# tinypico-fc.net
KiCad netlist of a schematic drawn in EAGLE
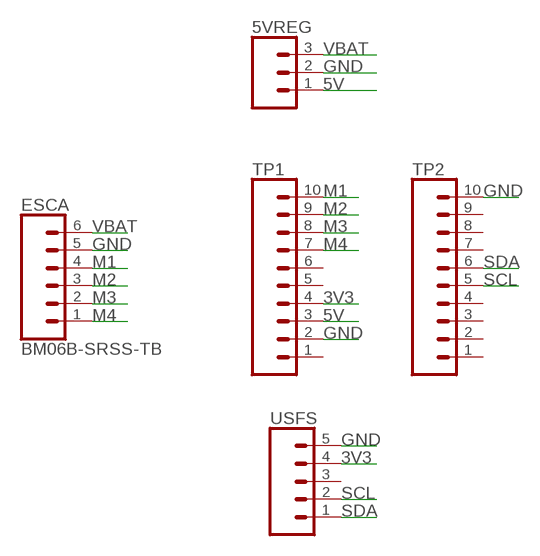
[diagram p0: schematic, sheet 1]

(export (version "E")
  (design (tool "Eeschema 10.0.6"))
  (components
    (comp (ref "5VREG")
      (value "CONN_031X03_NO_SILK")
      (footprint "eagle-import:1X03_NO_SILK")
      (libsource (lib "eagle-import") (part "CONN_031X03_NO_SILK"))
    )
    (comp (ref "ESC")
      (value "BM06B-SRSS-TB")
      (footprint "eagle-import:JST-6-SMD-HORI-1.0MM")
      (libsource (lib "eagle-import") (part "JST_6_PIN_HORIZONTAL"))
    )
    (comp (ref "TP1")
      (value "CONN_10NO_SILK_PTH_FEMALE")
      (footprint "eagle-import:1X10_NO_SILK")
      (libsource (lib "eagle-import") (part "CONN_10NO_SILK_PTH_FEMALE"))
    )
    (comp (ref "TP2")
      (value "CONN_10NO_SILK_PTH_FEMALE")
      (footprint "eagle-import:1X10_NO_SILK")
      (libsource (lib "eagle-import") (part "CONN_10NO_SILK_PTH_FEMALE"))
    )
    (comp (ref "USFS")
      (value "CONN_05NO_SILK")
      (footprint "eagle-import:1X05_NO_SILK")
      (libsource (lib "eagle-import") (part "CONN_05NO_SILK"))
    )
  )
  (nets
    (net (code "1") (name "/3V3") (class "Default")
      (node (ref "TP1") (pin "4") (pinfunction "4_4") (pintype "passive"))
      (node (ref "USFS") (pin "4") (pinfunction "4_4") (pintype "passive"))
    )
    (net (code "2") (name "/5V") (class "Default")
      (node (ref "5VREG") (pin "1") (pinfunction "1_1") (pintype "passive"))
      (node (ref "TP1") (pin "3") (pinfunction "3_3") (pintype "passive"))
    )
    (net (code "3") (name "/GND") (class "Default")
      (node (ref "5VREG") (pin "2") (pinfunction "2_2") (pintype "passive"))
      (node (ref "ESC") (pin "5") (pinfunction "5_5") (pintype "passive"))
      (node (ref "TP1") (pin "2") (pinfunction "2_2") (pintype "passive"))
      (node (ref "TP2") (pin "10") (pinfunction "10_10") (pintype "passive"))
      (node (ref "USFS") (pin "5") (pinfunction "5_5") (pintype "passive"))
    )
    (net (code "4") (name "/M1") (class "Default")
      (node (ref "ESC") (pin "4") (pinfunction "4_4") (pintype "passive"))
      (node (ref "TP1") (pin "10") (pinfunction "10_10") (pintype "passive"))
    )
    (net (code "5") (name "/M2") (class "Default")
      (node (ref "ESC") (pin "3") (pinfunction "3_3") (pintype "passive"))
      (node (ref "TP1") (pin "9") (pinfunction "9_9") (pintype "passive"))
    )
    (net (code "6") (name "/M3") (class "Default")
      (node (ref "ESC") (pin "2") (pinfunction "2_2") (pintype "passive"))
      (node (ref "TP1") (pin "8") (pinfunction "8_8") (pintype "passive"))
    )
    (net (code "7") (name "/M4") (class "Default")
      (node (ref "ESC") (pin "1") (pinfunction "1_1") (pintype "passive"))
      (node (ref "TP1") (pin "7") (pinfunction "7_7") (pintype "passive"))
    )
    (net (code "8") (name "/SCL") (class "Default")
      (node (ref "TP2") (pin "5") (pinfunction "5_5") (pintype "passive"))
      (node (ref "USFS") (pin "2") (pinfunction "2_2") (pintype "passive"))
    )
    (net (code "9") (name "/SDA") (class "Default")
      (node (ref "TP2") (pin "6") (pinfunction "6_6") (pintype "passive"))
      (node (ref "USFS") (pin "1") (pinfunction "1_1") (pintype "passive"))
    )
    (net (code "10") (name "/VBAT") (class "Default")
      (node (ref "5VREG") (pin "3") (pinfunction "3_3") (pintype "passive"))
      (node (ref "ESC") (pin "6") (pinfunction "6_6") (pintype "passive"))
    )
    (net (code "11") (name "unconnected-(TP1-Pad1)") (class "Default")
      (node (ref "TP1") (pin "1") (pinfunction "1_1") (pintype "passive"))
    )
    (net (code "12") (name "unconnected-(TP1-Pad5)") (class "Default")
      (node (ref "TP1") (pin "5") (pinfunction "5_5") (pintype "passive"))
    )
    (net (code "13") (name "unconnected-(TP1-Pad6)") (class "Default")
      (node (ref "TP1") (pin "6") (pinfunction "6_6") (pintype "passive"))
    )
    (net (code "14") (name "unconnected-(TP2-Pad1)") (class "Default")
      (node (ref "TP2") (pin "1") (pinfunction "1_1") (pintype "passive"))
    )
    (net (code "15") (name "unconnected-(TP2-Pad2)") (class "Default")
      (node (ref "TP2") (pin "2") (pinfunction "2_2") (pintype "passive"))
    )
    (net (code "16") (name "unconnected-(TP2-Pad3)") (class "Default")
      (node (ref "TP2") (pin "3") (pinfunction "3_3") (pintype "passive"))
    )
    (net (code "17") (name "unconnected-(TP2-Pad4)") (class "Default")
      (node (ref "TP2") (pin "4") (pinfunction "4_4") (pintype "passive"))
    )
    (net (code "18") (name "unconnected-(TP2-Pad7)") (class "Default")
      (node (ref "TP2") (pin "7") (pinfunction "7_7") (pintype "passive"))
    )
    (net (code "19") (name "unconnected-(TP2-Pad8)") (class "Default")
      (node (ref "TP2") (pin "8") (pinfunction "8_8") (pintype "passive"))
    )
    (net (code "20") (name "unconnected-(TP2-Pad9)") (class "Default")
      (node (ref "TP2") (pin "9") (pinfunction "9_9") (pintype "passive"))
    )
    (net (code "21") (name "unconnected-(USFS-Pad3)") (class "Default")
      (node (ref "USFS") (pin "3") (pinfunction "3_3") (pintype "passive"))
    )
  )
)
